# BUS_TEST.net
KiCad netlist of a schematic drawn in EAGLE
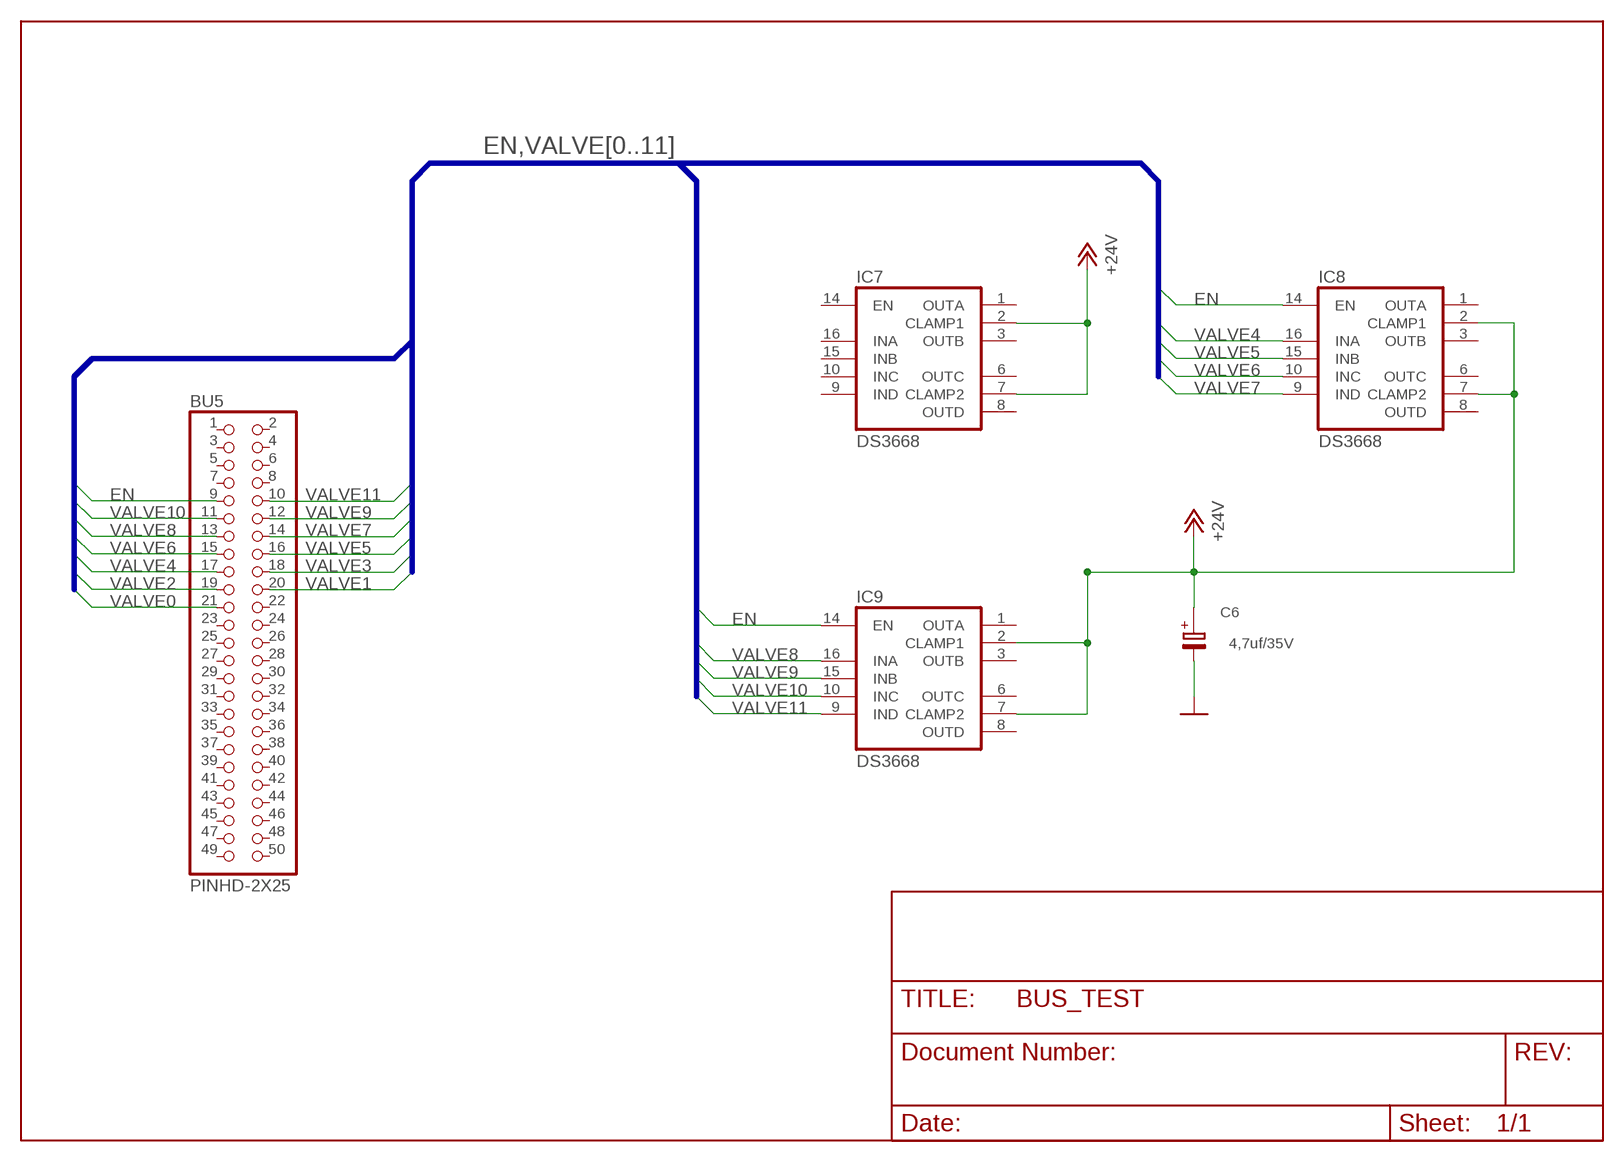
[diagram p0: schematic, sheet 1]

(export (version "E")
  (design (tool "Eeschema 10.0.6"))
  (components
    (comp (ref "BU5")
      (value "PINHD-2X25")
      (footprint "eagle-import:2X25")
      (libsource (lib "eagle-import") (part "PINHD-2X25"))
    )
    (comp (ref "C6")
      (value "4,7uf/35V")
      (footprint "eagle-import:E2,5-5")
      (libsource (lib "eagle-import") (part "E2-5@1"))
    )
    (comp (ref "IC7")
      (value "DS3668")
      (footprint "eagle-import:DIL-16")
      (libsource (lib "eagle-import") (part "DS3668"))
    )
    (comp (ref "IC8")
      (value "DS3668")
      (footprint "eagle-import:DIL-16")
      (libsource (lib "eagle-import") (part "DS3668"))
    )
    (comp (ref "IC9")
      (value "DS3668")
      (footprint "eagle-import:DIL-16")
      (libsource (lib "eagle-import") (part "DS3668"))
    )
  )
  (nets
    (net (code "13") (name "+24V") (class "Default")
      (node (ref "C6") (pin "+") (pinfunction "+_+") (pintype "passive"))
      (node (ref "IC7") (pin "2") (pinfunction "CLAMP1_2") (pintype "bidirectional"))
      (node (ref "IC7") (pin "7") (pinfunction "CLAMP2_7") (pintype "bidirectional"))
      (node (ref "IC8") (pin "2") (pinfunction "CLAMP1_2") (pintype "bidirectional"))
      (node (ref "IC8") (pin "7") (pinfunction "CLAMP2_7") (pintype "bidirectional"))
      (node (ref "IC9") (pin "2") (pinfunction "CLAMP1_2") (pintype "bidirectional"))
      (node (ref "IC9") (pin "7") (pinfunction "CLAMP2_7") (pintype "bidirectional"))
    )
    (net (code "14") (name "/EN") (class "Default")
      (node (ref "BU5") (pin "9") (pinfunction "9_9") (pintype "passive"))
      (node (ref "IC8") (pin "14") (pinfunction "EN_14") (pintype "input"))
      (node (ref "IC9") (pin "14") (pinfunction "EN_14") (pintype "input"))
    )
    (net (code "16") (name "/VALVE0") (class "Default")
      (node (ref "BU5") (pin "21") (pinfunction "21_21") (pintype "passive"))
    )
    (net (code "17") (name "/VALVE1") (class "Default")
      (node (ref "BU5") (pin "20") (pinfunction "20_20") (pintype "passive"))
    )
    (net (code "18") (name "/VALVE2") (class "Default")
      (node (ref "BU5") (pin "19") (pinfunction "19_19") (pintype "passive"))
    )
    (net (code "19") (name "/VALVE3") (class "Default")
      (node (ref "BU5") (pin "18") (pinfunction "18_18") (pintype "passive"))
    )
    (net (code "20") (name "/VALVE4") (class "Default")
      (node (ref "BU5") (pin "17") (pinfunction "17_17") (pintype "passive"))
      (node (ref "IC8") (pin "16") (pinfunction "INA_16") (pintype "input"))
    )
    (net (code "21") (name "/VALVE5") (class "Default")
      (node (ref "BU5") (pin "16") (pinfunction "16_16") (pintype "passive"))
      (node (ref "IC8") (pin "15") (pinfunction "INB_15") (pintype "input"))
    )
    (net (code "22") (name "/VALVE6") (class "Default")
      (node (ref "BU5") (pin "15") (pinfunction "15_15") (pintype "passive"))
      (node (ref "IC8") (pin "10") (pinfunction "INC_10") (pintype "input"))
    )
    (net (code "23") (name "/VALVE7") (class "Default")
      (node (ref "BU5") (pin "14") (pinfunction "14_14") (pintype "passive"))
      (node (ref "IC8") (pin "9") (pinfunction "IND_9") (pintype "input"))
    )
    (net (code "24") (name "/VALVE8") (class "Default")
      (node (ref "BU5") (pin "13") (pinfunction "13_13") (pintype "passive"))
      (node (ref "IC9") (pin "16") (pinfunction "INA_16") (pintype "input"))
    )
    (net (code "25") (name "/VALVE9") (class "Default")
      (node (ref "BU5") (pin "12") (pinfunction "12_12") (pintype "passive"))
      (node (ref "IC9") (pin "15") (pinfunction "INB_15") (pintype "input"))
    )
    (net (code "26") (name "/VALVE10") (class "Default")
      (node (ref "BU5") (pin "11") (pinfunction "11_11") (pintype "passive"))
      (node (ref "IC9") (pin "10") (pinfunction "INC_10") (pintype "input"))
    )
    (net (code "27") (name "/VALVE11") (class "Default")
      (node (ref "BU5") (pin "10") (pinfunction "10_10") (pintype "passive"))
      (node (ref "IC9") (pin "9") (pinfunction "IND_9") (pintype "input"))
    )
    (net (code "28") (name "GND") (class "Default")
      (node (ref "C6") (pin "-") (pinfunction "-_-") (pintype "passive"))
    )
    (net (code "29") (name "unconnected-(BU5-Pad1)") (class "Default")
      (node (ref "BU5") (pin "1") (pinfunction "1_1") (pintype "passive"))
    )
    (net (code "30") (name "unconnected-(BU5-Pad2)") (class "Default")
      (node (ref "BU5") (pin "2") (pinfunction "2_2") (pintype "passive"))
    )
    (net (code "31") (name "unconnected-(BU5-Pad3)") (class "Default")
      (node (ref "BU5") (pin "3") (pinfunction "3_3") (pintype "passive"))
    )
    (net (code "32") (name "unconnected-(BU5-Pad4)") (class "Default")
      (node (ref "BU5") (pin "4") (pinfunction "4_4") (pintype "passive"))
    )
    (net (code "33") (name "unconnected-(BU5-Pad5)") (class "Default")
      (node (ref "BU5") (pin "5") (pinfunction "5_5") (pintype "passive"))
    )
    (net (code "34") (name "unconnected-(BU5-Pad6)") (class "Default")
      (node (ref "BU5") (pin "6") (pinfunction "6_6") (pintype "passive"))
    )
    (net (code "35") (name "unconnected-(BU5-Pad7)") (class "Default")
      (node (ref "BU5") (pin "7") (pinfunction "7_7") (pintype "passive"))
    )
    (net (code "36") (name "unconnected-(BU5-Pad8)") (class "Default")
      (node (ref "BU5") (pin "8") (pinfunction "8_8") (pintype "passive"))
    )
    (net (code "37") (name "unconnected-(BU5-Pad22)") (class "Default")
      (node (ref "BU5") (pin "22") (pinfunction "22_22") (pintype "passive"))
    )
    (net (code "38") (name "unconnected-(BU5-Pad23)") (class "Default")
      (node (ref "BU5") (pin "23") (pinfunction "23_23") (pintype "passive"))
    )
    (net (code "39") (name "unconnected-(BU5-Pad24)") (class "Default")
      (node (ref "BU5") (pin "24") (pinfunction "24_24") (pintype "passive"))
    )
    (net (code "40") (name "unconnected-(BU5-Pad25)") (class "Default")
      (node (ref "BU5") (pin "25") (pinfunction "25_25") (pintype "passive"))
    )
    (net (code "41") (name "unconnected-(BU5-Pad26)") (class "Default")
      (node (ref "BU5") (pin "26") (pinfunction "26_26") (pintype "passive"))
    )
    (net (code "42") (name "unconnected-(BU5-Pad27)") (class "Default")
      (node (ref "BU5") (pin "27") (pinfunction "27_27") (pintype "passive"))
    )
    (net (code "43") (name "unconnected-(BU5-Pad28)") (class "Default")
      (node (ref "BU5") (pin "28") (pinfunction "28_28") (pintype "passive"))
    )
    (net (code "44") (name "unconnected-(BU5-Pad29)") (class "Default")
      (node (ref "BU5") (pin "29") (pinfunction "29_29") (pintype "passive"))
    )
    (net (code "45") (name "unconnected-(BU5-Pad30)") (class "Default")
      (node (ref "BU5") (pin "30") (pinfunction "30_30") (pintype "passive"))
    )
    (net (code "46") (name "unconnected-(BU5-Pad31)") (class "Default")
      (node (ref "BU5") (pin "31") (pinfunction "31_31") (pintype "passive"))
    )
    (net (code "47") (name "unconnected-(BU5-Pad32)") (class "Default")
      (node (ref "BU5") (pin "32") (pinfunction "32_32") (pintype "passive"))
    )
    (net (code "48") (name "unconnected-(BU5-Pad33)") (class "Default")
      (node (ref "BU5") (pin "33") (pinfunction "33_33") (pintype "passive"))
    )
    (net (code "49") (name "unconnected-(BU5-Pad34)") (class "Default")
      (node (ref "BU5") (pin "34") (pinfunction "34_34") (pintype "passive"))
    )
    (net (code "50") (name "unconnected-(BU5-Pad35)") (class "Default")
      (node (ref "BU5") (pin "35") (pinfunction "35_35") (pintype "passive"))
    )
    (net (code "51") (name "unconnected-(BU5-Pad36)") (class "Default")
      (node (ref "BU5") (pin "36") (pinfunction "36_36") (pintype "passive"))
    )
    (net (code "52") (name "unconnected-(BU5-Pad37)") (class "Default")
      (node (ref "BU5") (pin "37") (pinfunction "37_37") (pintype "passive"))
    )
    (net (code "53") (name "unconnected-(BU5-Pad38)") (class "Default")
      (node (ref "BU5") (pin "38") (pinfunction "38_38") (pintype "passive"))
    )
    (net (code "54") (name "unconnected-(BU5-Pad39)") (class "Default")
      (node (ref "BU5") (pin "39") (pinfunction "39_39") (pintype "passive"))
    )
    (net (code "55") (name "unconnected-(BU5-Pad40)") (class "Default")
      (node (ref "BU5") (pin "40") (pinfunction "40_40") (pintype "passive"))
    )
    (net (code "56") (name "unconnected-(BU5-Pad41)") (class "Default")
      (node (ref "BU5") (pin "41") (pinfunction "41_41") (pintype "passive"))
    )
    (net (code "57") (name "unconnected-(BU5-Pad42)") (class "Default")
      (node (ref "BU5") (pin "42") (pinfunction "42_42") (pintype "passive"))
    )
    (net (code "58") (name "unconnected-(BU5-Pad43)") (class "Default")
      (node (ref "BU5") (pin "43") (pinfunction "43_43") (pintype "passive"))
    )
    (net (code "59") (name "unconnected-(BU5-Pad44)") (class "Default")
      (node (ref "BU5") (pin "44") (pinfunction "44_44") (pintype "passive"))
    )
    (net (code "60") (name "unconnected-(BU5-Pad45)") (class "Default")
      (node (ref "BU5") (pin "45") (pinfunction "45_45") (pintype "passive"))
    )
    (net (code "61") (name "unconnected-(BU5-Pad46)") (class "Default")
      (node (ref "BU5") (pin "46") (pinfunction "46_46") (pintype "passive"))
    )
    (net (code "62") (name "unconnected-(BU5-Pad47)") (class "Default")
      (node (ref "BU5") (pin "47") (pinfunction "47_47") (pintype "passive"))
    )
    (net (code "63") (name "unconnected-(BU5-Pad48)") (class "Default")
      (node (ref "BU5") (pin "48") (pinfunction "48_48") (pintype "passive"))
    )
    (net (code "64") (name "unconnected-(BU5-Pad49)") (class "Default")
      (node (ref "BU5") (pin "49") (pinfunction "49_49") (pintype "passive"))
    )
    (net (code "65") (name "unconnected-(BU5-Pad50)") (class "Default")
      (node (ref "BU5") (pin "50") (pinfunction "50_50") (pintype "passive"))
    )
    (net (code "66") (name "unconnected-(IC7A-EN-Pad14)") (class "Default")
      (node (ref "IC7") (pin "14") (pinfunction "EN_14") (pintype "input"))
    )
    (net (code "67") (name "unconnected-(IC7A-INA-Pad16)") (class "Default")
      (node (ref "IC7") (pin "16") (pinfunction "INA_16") (pintype "input"))
    )
    (net (code "68") (name "unconnected-(IC7A-INB-Pad15)") (class "Default")
      (node (ref "IC7") (pin "15") (pinfunction "INB_15") (pintype "input"))
    )
    (net (code "69") (name "unconnected-(IC7A-INC-Pad10)") (class "Default")
      (node (ref "IC7") (pin "10") (pinfunction "INC_10") (pintype "input"))
    )
    (net (code "70") (name "unconnected-(IC7A-IND-Pad9)") (class "Default")
      (node (ref "IC7") (pin "9") (pinfunction "IND_9") (pintype "input"))
    )
    (net (code "71") (name "unconnected-(IC7A-OUTA-Pad1)") (class "Default")
      (node (ref "IC7") (pin "1") (pinfunction "OUTA_1") (pintype "bidirectional"))
    )
    (net (code "72") (name "unconnected-(IC7A-OUTB-Pad3)") (class "Default")
      (node (ref "IC7") (pin "3") (pinfunction "OUTB_3") (pintype "bidirectional"))
    )
    (net (code "73") (name "unconnected-(IC7A-OUTC-Pad6)") (class "Default")
      (node (ref "IC7") (pin "6") (pinfunction "OUTC_6") (pintype "bidirectional"))
    )
    (net (code "74") (name "unconnected-(IC7A-OUTD-Pad8)") (class "Default")
      (node (ref "IC7") (pin "8") (pinfunction "OUTD_8") (pintype "bidirectional"))
    )
    (net (code "75") (name "unconnected-(IC8A-OUTA-Pad1)") (class "Default")
      (node (ref "IC8") (pin "1") (pinfunction "OUTA_1") (pintype "bidirectional"))
    )
    (net (code "76") (name "unconnected-(IC8A-OUTB-Pad3)") (class "Default")
      (node (ref "IC8") (pin "3") (pinfunction "OUTB_3") (pintype "bidirectional"))
    )
    (net (code "77") (name "unconnected-(IC8A-OUTC-Pad6)") (class "Default")
      (node (ref "IC8") (pin "6") (pinfunction "OUTC_6") (pintype "bidirectional"))
    )
    (net (code "78") (name "unconnected-(IC8A-OUTD-Pad8)") (class "Default")
      (node (ref "IC8") (pin "8") (pinfunction "OUTD_8") (pintype "bidirectional"))
    )
    (net (code "79") (name "unconnected-(IC9A-OUTA-Pad1)") (class "Default")
      (node (ref "IC9") (pin "1") (pinfunction "OUTA_1") (pintype "bidirectional"))
    )
    (net (code "80") (name "unconnected-(IC9A-OUTB-Pad3)") (class "Default")
      (node (ref "IC9") (pin "3") (pinfunction "OUTB_3") (pintype "bidirectional"))
    )
    (net (code "81") (name "unconnected-(IC9A-OUTC-Pad6)") (class "Default")
      (node (ref "IC9") (pin "6") (pinfunction "OUTC_6") (pintype "bidirectional"))
    )
    (net (code "82") (name "unconnected-(IC9A-OUTD-Pad8)") (class "Default")
      (node (ref "IC9") (pin "8") (pinfunction "OUTD_8") (pintype "bidirectional"))
    )
  )
)
